# Power.net
KiCad netlist of a schematic drawn in Altium Designer
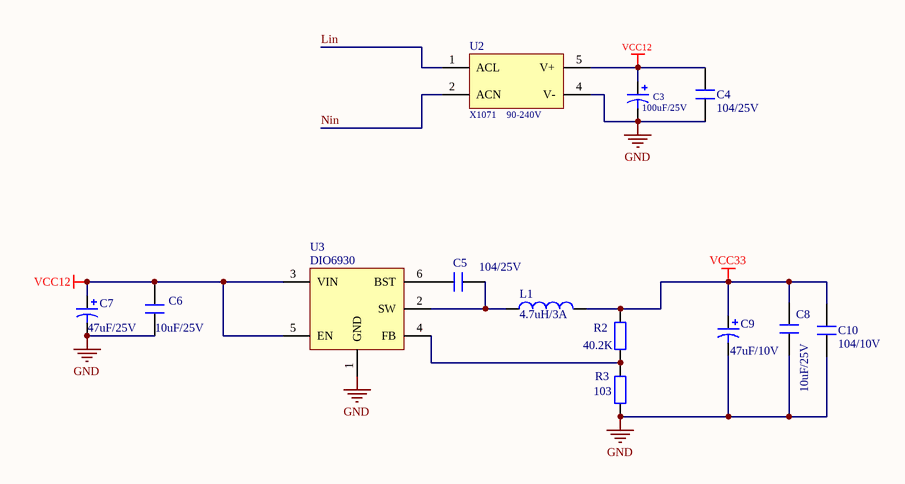
[diagram p0: Power.SchDoc]

(export (version "E")
  (design (tool "Eeschema 10.0.6"))
  (components
    (comp (ref "C3")
      (value "100uF/25V")
      (footprint "CAPPIND06")
      (description "Polarized Capacitor (Radial)")
      (fields (field (name "PUBLISHER") "Altium Limited"))
      (libsource (lib "Miscellaneous Devices") (part "Cap Pol1"))
    )
    (comp (ref "C4") (value "104/25V") (footprint "0603R") (libsource (lib "ES_Schematic") (part "CAP_1")))
    (comp (ref "C5") (value "104/25V") (footprint "0603R") (libsource (lib "ES_Schematic") (part "CAP_1")))
    (comp (ref "C6") (value "10uF/25V") (footprint "0603R") (libsource (lib "ES_Schematic") (part "CAP")))
    (comp (ref "C7")
      (value "47uF/25V")
      (footprint "0805R")
      (description "Polarized Capacitor (Radial)")
      (fields (field (name "PUBLISHER") "Altium Limited"))
      (libsource (lib "Miscellaneous Devices") (part "Cap Pol1"))
    )
    (comp (ref "C8") (value "10uF/25V") (footprint "0603R") (libsource (lib "ES_Schematic") (part "CAP")))
    (comp (ref "C9")
      (value "47uF/10V")
      (footprint "0805R")
      (description "Polarized Capacitor (Radial)")
      (fields (field (name "PUBLISHER") "Altium Limited"))
      (libsource (lib "Miscellaneous Devices") (part "Cap Pol1"))
    )
    (comp (ref "C10") (value "104/10V") (footprint "0603R") (libsource (lib "ES_Schematic") (part "CAP_1")))
    (comp (ref "L1")
      (value "4.7uH/3A")
      (footprint "贴片电感5020")
      (description "Inductor")
      (fields (field (name "PUBLISHER") "Altium Limited"))
      (libsource (lib "Miscellaneous Devices") (part "Inductor"))
    )
    (comp (ref "R2")
      (value "40.2K")
      (footprint "0603R")
      (description "Resistor")
      (fields (field (name "PUBLISHER") "Altium Limited"))
      (libsource (lib "Miscellaneous Devices") (part "Res2"))
    )
    (comp (ref "R3")
      (value "103")
      (footprint "0603R")
      (description "Resistor")
      (fields (field (name "PUBLISHER") "Altium Limited"))
      (libsource (lib "Miscellaneous Devices") (part "Res2"))
    )
    (comp (ref "U2")
      (value "X1071    90-240V")
      (footprint "X1071")
      (libsource (lib "sangjian") (part "AD2DC_EMC"))
    )
    (comp (ref "U3")
      (value "DIO6930")
      (footprint "SOT-23-6DBV")
      (libsource (lib "ES_Schematic") (part "BL8032"))
    )
  )
  (nets
    (net (code "1") (name "/Lin") (class "Default")
      (node (ref "U2") (pin "1") (pinfunction "ACL_1") (pintype "passive"))
    )
    (net (code "2") (name "/Nin") (class "Default")
      (node (ref "U2") (pin "2") (pinfunction "ACN_2") (pintype "passive"))
    )
    (net (code "3") (name "GND") (class "Default")
      (node (ref "C10") (pin "1") (pinfunction "1_1") (pintype "passive"))
      (node (ref "C3") (pin "2") (pinfunction "2_2") (pintype "passive"))
      (node (ref "C4") (pin "1") (pinfunction "1_1") (pintype "passive"))
      (node (ref "C6") (pin "1") (pinfunction "1_1") (pintype "passive"))
      (node (ref "C7") (pin "2") (pinfunction "2_2") (pintype "passive"))
      (node (ref "C8") (pin "1") (pinfunction "1_1") (pintype "passive"))
      (node (ref "C9") (pin "2") (pinfunction "2_2") (pintype "passive"))
      (node (ref "R3") (pin "2") (pinfunction "2_2") (pintype "passive"))
      (node (ref "U2") (pin "4") (pinfunction "V-_4") (pintype "passive"))
      (node (ref "U3") (pin "1") (pinfunction "GND_1") (pintype "passive"))
    )
    (net (code "4") (name "Net-(U3-BST)") (class "Default")
      (node (ref "C5") (pin "2") (pinfunction "2_2") (pintype "passive"))
      (node (ref "U3") (pin "6") (pinfunction "BST_6") (pintype "passive"))
    )
    (net (code "5") (name "Net-(U3-FB)") (class "Default")
      (node (ref "R2") (pin "2") (pinfunction "2_2") (pintype "passive"))
      (node (ref "R3") (pin "1") (pinfunction "1_1") (pintype "passive"))
      (node (ref "U3") (pin "4") (pinfunction "FB_4") (pintype "passive"))
    )
    (net (code "6") (name "Net-(U3-SW)") (class "Default")
      (node (ref "C5") (pin "1") (pinfunction "1_1") (pintype "passive"))
      (node (ref "L1") (pin "1") (pinfunction "1_1") (pintype "passive"))
      (node (ref "U3") (pin "2") (pinfunction "SW_2") (pintype "passive"))
    )
    (net (code "7") (name "VCC12") (class "Default")
      (node (ref "C3") (pin "1") (pinfunction "1_1") (pintype "passive"))
      (node (ref "C4") (pin "2") (pinfunction "2_2") (pintype "passive"))
      (node (ref "C6") (pin "2") (pinfunction "2_2") (pintype "passive"))
      (node (ref "C7") (pin "1") (pinfunction "1_1") (pintype "passive"))
      (node (ref "U2") (pin "5") (pinfunction "V+_5") (pintype "passive"))
      (node (ref "U3") (pin "3") (pinfunction "VIN_3") (pintype "passive"))
      (node (ref "U3") (pin "5") (pinfunction "EN_5") (pintype "passive"))
    )
    (net (code "8") (name "VCC33") (class "Default")
      (node (ref "C10") (pin "2") (pinfunction "2_2") (pintype "passive"))
      (node (ref "C8") (pin "2") (pinfunction "2_2") (pintype "passive"))
      (node (ref "C9") (pin "1") (pinfunction "1_1") (pintype "passive"))
      (node (ref "L1") (pin "2") (pinfunction "2_2") (pintype "passive"))
      (node (ref "R2") (pin "1") (pinfunction "1_1") (pintype "passive"))
    )
  )
)
